# temperature-box_2020-09-28_12-37-06.net
KiCad netlist of a schematic drawn in EasyEDA
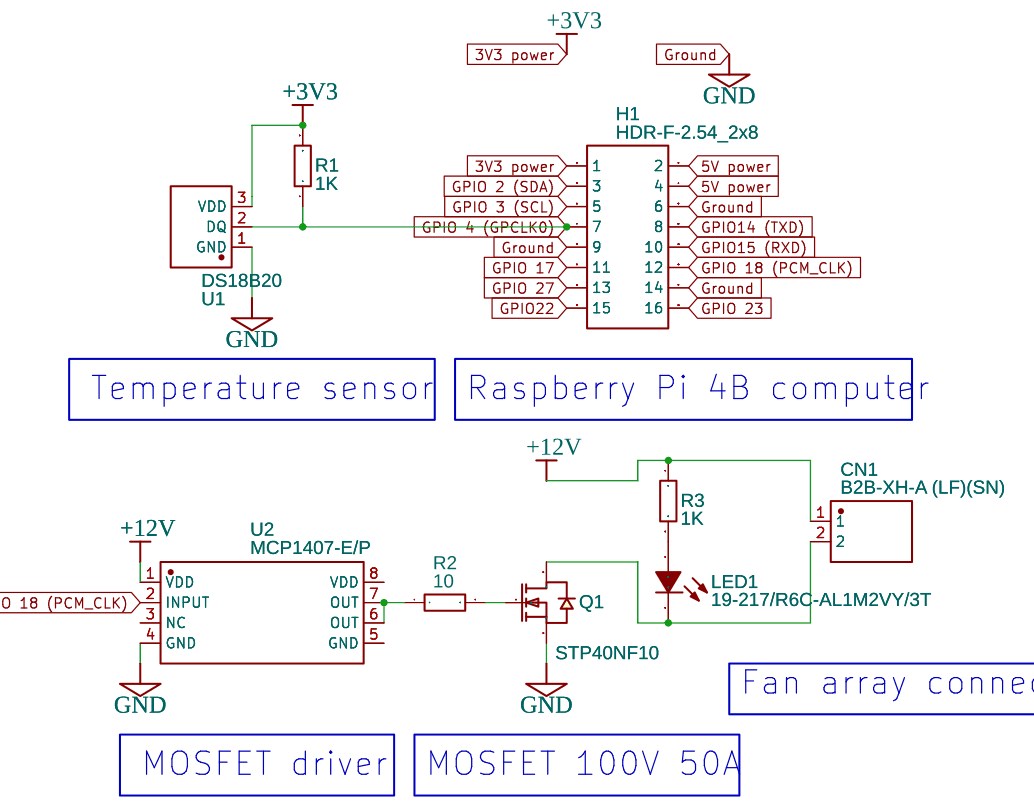
[diagram p0: schematic sheet]

(export (version "E")
  (design (tool "Eeschema 10.0.6"))
  (components
    (comp (ref "CN1")
      (value "B2B-XH-A (LF)(SN)")
      (fields (field (name "BOM_Supplier Part") "C158012"))
      (libsource (lib "") (part "B2B-XH-A (LF)(SN)"))
    )
    (comp (ref "H1")
      (value "HDR-F-2.54_2x8")
      (fields (field (name "BOM_Supplier Part") "C30734"))
      (libsource (lib "") (part "HDR-F-2.54_2x8"))
    )
    (comp (ref "LED1")
      (value "19-217/R6C-AL1M2VY/3T")
      (fields (field (name "BOM_Supplier Part") "C72044"))
      (libsource (lib "") (part "19-217/R6C-AL1M2VY/3T"))
    )
    (comp (ref "Q1")
      (value "STP40NF10")
      (fields (field (name "BOM_Supplier Part") "C495254"))
      (libsource (lib "") (part "STP40NF10"))
    )
    (comp (ref "R1")
      (value "1K")
      (fields
        (field (name "BOM_Manufacturer Part") "0805W8F1001T5E")
        (field (name "BOM_Supplier Part") "C17513")
      )
      (libsource (lib "") (part "0805W8F1001T5E"))
    )
    (comp (ref "R2")
      (value "10")
      (fields
        (field (name "BOM_Manufacturer Part") "MFR0W4F100JA50")
        (field (name "BOM_Supplier Part") "C57437")
      )
      (libsource (lib "") (part "MFR0W4F100JA50"))
    )
    (comp (ref "R3")
      (value "1K")
      (fields
        (field (name "BOM_Manufacturer Part") "MFR0W4F1001A50")
        (field (name "BOM_Supplier Part") "C57435")
      )
      (libsource (lib "") (part "MFR0W4F1001A50"))
    )
    (comp (ref "U1")
      (value "DS18B20")
      (fields (field (name "BOM_Supplier Part") "C376006"))
      (libsource (lib "") (part "DS18B20"))
    )
    (comp (ref "U2")
      (value "MCP1407-E/P")
      (fields (field (name "BOM_Supplier Part") "C185573"))
      (libsource (lib "") (part "MCP1407-E/P"))
    )
  )
  (nets
    (net (code "1") (name "+12V") (class "Default")
      (node (ref "CN1") (pin "1") (pinfunction "1_1") (pintype "unspecified"))
      (node (ref "R3") (pin "1") (pinfunction "1_1") (pintype "input"))
      (node (ref "U2") (pin "1") (pinfunction "VDD_1") (pintype "unspecified"))
    )
    (net (code "2") (name "3V3 power") (class "Default")
      (node (ref "H1") (pin "1") (pinfunction "1_1") (pintype "input"))
      (node (ref "R1") (pin "2") (pinfunction "2_2") (pintype "input"))
      (node (ref "U1") (pin "3") (pinfunction "VDD_3") (pintype "unspecified"))
    )
    (net (code "3") (name "5V power") (class "Default")
      (node (ref "H1") (pin "2") (pinfunction "2_2") (pintype "input"))
      (node (ref "H1") (pin "4") (pinfunction "4_4") (pintype "input"))
    )
    (net (code "4") (name "GPIO 2 (SDA)") (class "Default")
      (node (ref "H1") (pin "3") (pinfunction "3_3") (pintype "input"))
    )
    (net (code "5") (name "GPIO 3 (SCL)") (class "Default")
      (node (ref "H1") (pin "5") (pinfunction "5_5") (pintype "input"))
    )
    (net (code "6") (name "GPIO 4 (GPCLK0)") (class "Default")
      (node (ref "H1") (pin "7") (pinfunction "7_7") (pintype "input"))
      (node (ref "R1") (pin "1") (pinfunction "1_1") (pintype "input"))
      (node (ref "U1") (pin "2") (pinfunction "DQ_2") (pintype "unspecified"))
    )
    (net (code "7") (name "GPIO 17") (class "Default")
      (node (ref "H1") (pin "11") (pinfunction "11_11") (pintype "input"))
    )
    (net (code "8") (name "GPIO 18 (PCM_CLK)") (class "Default")
      (node (ref "H1") (pin "12") (pinfunction "12_12") (pintype "input"))
      (node (ref "U2") (pin "2") (pinfunction "INPUT_2") (pintype "unspecified"))
    )
    (net (code "9") (name "GPIO 23") (class "Default")
      (node (ref "H1") (pin "16") (pinfunction "16_16") (pintype "input"))
    )
    (net (code "10") (name "GPIO 27") (class "Default")
      (node (ref "H1") (pin "13") (pinfunction "13_13") (pintype "input"))
    )
    (net (code "11") (name "GPIO14 (TXD)") (class "Default")
      (node (ref "H1") (pin "8") (pinfunction "8_8") (pintype "input"))
    )
    (net (code "12") (name "GPIO15 (RXD)") (class "Default")
      (node (ref "H1") (pin "10") (pinfunction "10_10") (pintype "input"))
    )
    (net (code "13") (name "GPIO22") (class "Default")
      (node (ref "H1") (pin "15") (pinfunction "15_15") (pintype "input"))
    )
    (net (code "14") (name "Ground") (class "Default")
      (node (ref "H1") (pin "14") (pinfunction "14_14") (pintype "input"))
      (node (ref "H1") (pin "6") (pinfunction "6_6") (pintype "input"))
      (node (ref "H1") (pin "9") (pinfunction "9_9") (pintype "input"))
      (node (ref "Q1") (pin "3") (pinfunction "S_3") (pintype "unspecified"))
      (node (ref "U1") (pin "1") (pinfunction "GND_1") (pintype "unspecified"))
      (node (ref "U2") (pin "4") (pinfunction "GND_4") (pintype "unspecified"))
    )
    (net (code "15") (name "Net-(LED1-A)") (class "Default")
      (node (ref "LED1") (pin "1") (pinfunction "A_1") (pintype "input"))
      (node (ref "R3") (pin "2") (pinfunction "2_2") (pintype "input"))
    )
    (net (code "16") (name "Net-(LED1-C)") (class "Default")
      (node (ref "CN1") (pin "2") (pinfunction "2_2") (pintype "unspecified"))
      (node (ref "LED1") (pin "2") (pinfunction "C_2") (pintype "input"))
      (node (ref "Q1") (pin "2") (pinfunction "D_2") (pintype "unspecified"))
    )
    (net (code "17") (name "Net-(Q1-G)") (class "Default")
      (node (ref "Q1") (pin "1") (pinfunction "G_1") (pintype "unspecified"))
      (node (ref "R2") (pin "2") (pinfunction "2_2") (pintype "input"))
    )
    (net (code "18") (name "Net-(R2-Pad1)") (class "Default")
      (node (ref "R2") (pin "1") (pinfunction "1_1") (pintype "input"))
      (node (ref "U2") (pin "6") (pinfunction "OUT_6") (pintype "unspecified"))
      (node (ref "U2") (pin "7") (pinfunction "OUT_7") (pintype "unspecified"))
    )
    (net (code "19") (name "unconnected-(U2-GND-Pad5)") (class "Default")
      (node (ref "U2") (pin "5") (pinfunction "GND_5") (pintype "unspecified"))
    )
    (net (code "20") (name "unconnected-(U2-NC-Pad3)") (class "Default")
      (node (ref "U2") (pin "3") (pinfunction "NC_3") (pintype "unspecified"))
    )
    (net (code "21") (name "unconnected-(U2-VDD-Pad8)") (class "Default")
      (node (ref "U2") (pin "8") (pinfunction "VDD_8") (pintype "unspecified"))
    )
  )
)
